# Nixie_Display.net
KiCad netlist of a schematic drawn in EAGLE
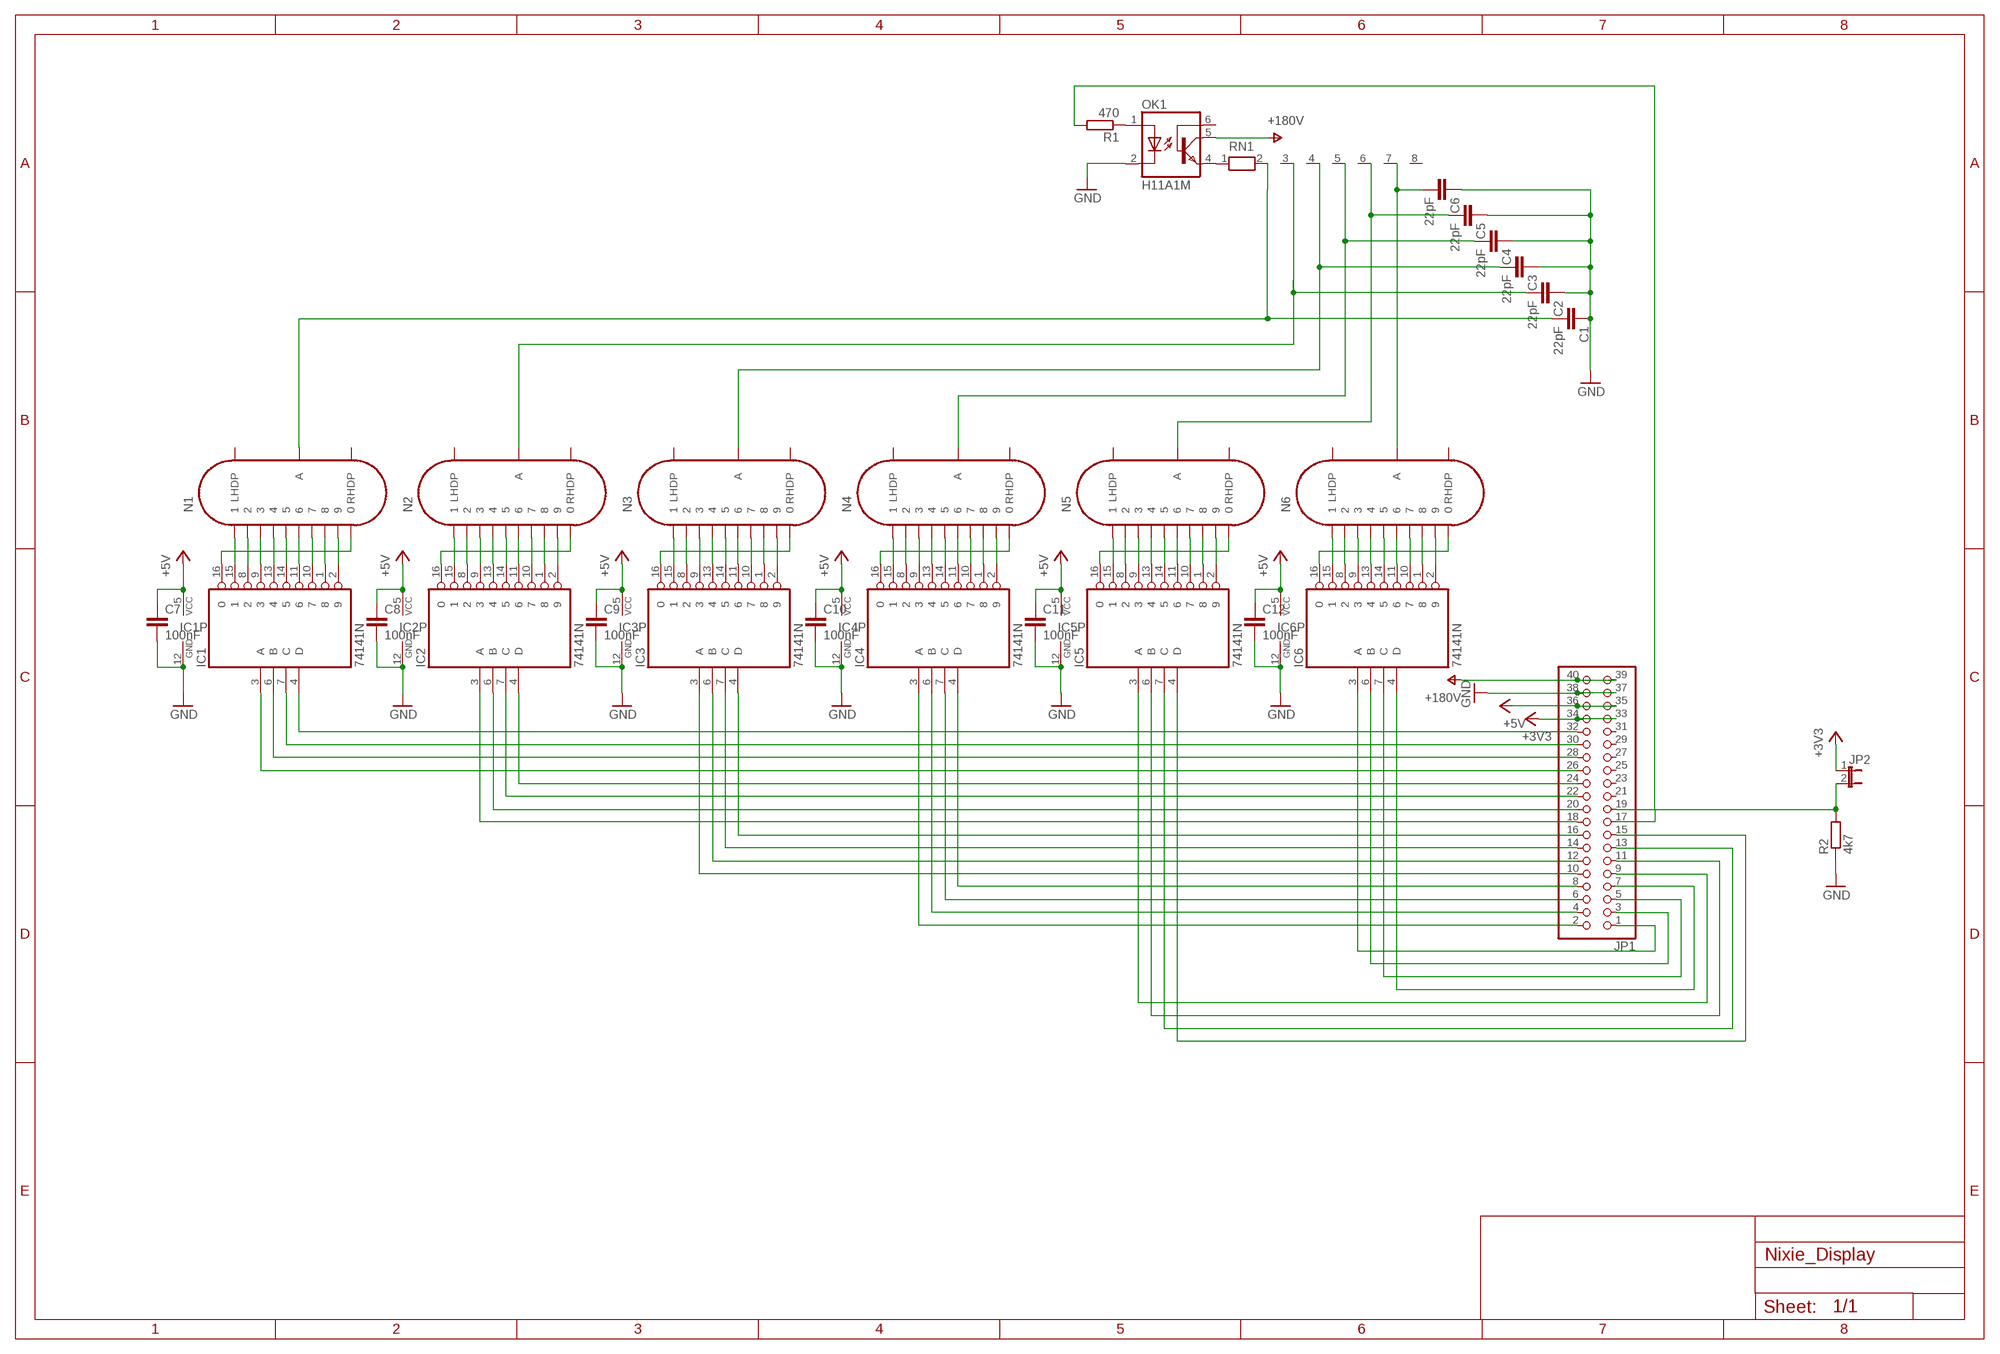
[diagram p0: schematic, sheet 1]

(export (version "E")
  (design (tool "Eeschema 10.0.6"))
  (components
    (comp (ref "C1")
      (value "22pF")
      (footprint "eagle-import:C025-025X050")
      (libsource (lib "eagle-import") (part "C-EU025-025X050"))
    )
    (comp (ref "C2")
      (value "22pF")
      (footprint "eagle-import:C025-025X050")
      (libsource (lib "eagle-import") (part "C-EU025-025X050"))
    )
    (comp (ref "C3")
      (value "22pF")
      (footprint "eagle-import:C025-025X050")
      (libsource (lib "eagle-import") (part "C-EU025-025X050"))
    )
    (comp (ref "C4")
      (value "22pF")
      (footprint "eagle-import:C025-025X050")
      (libsource (lib "eagle-import") (part "C-EU025-025X050"))
    )
    (comp (ref "C5")
      (value "22pF")
      (footprint "eagle-import:C025-025X050")
      (libsource (lib "eagle-import") (part "C-EU025-025X050"))
    )
    (comp (ref "C6")
      (value "22pF")
      (footprint "eagle-import:C025-025X050")
      (libsource (lib "eagle-import") (part "C-EU025-025X050"))
    )
    (comp (ref "C7")
      (value "100nF")
      (footprint "eagle-import:C050-025X075")
      (libsource (lib "eagle-import") (part "C-EU050-025X075"))
    )
    (comp (ref "C8")
      (value "100nF")
      (footprint "eagle-import:C050-025X075")
      (libsource (lib "eagle-import") (part "C-EU050-025X075"))
    )
    (comp (ref "C9")
      (value "100nF")
      (footprint "eagle-import:C050-025X075")
      (libsource (lib "eagle-import") (part "C-EU050-025X075"))
    )
    (comp (ref "C10")
      (value "100nF")
      (footprint "eagle-import:C050-025X075")
      (libsource (lib "eagle-import") (part "C-EU050-025X075"))
    )
    (comp (ref "C11")
      (value "100nF")
      (footprint "eagle-import:C050-025X075")
      (libsource (lib "eagle-import") (part "C-EU050-025X075"))
    )
    (comp (ref "C12")
      (value "100nF")
      (footprint "eagle-import:C050-025X075")
      (libsource (lib "eagle-import") (part "C-EU050-025X075"))
    )
    (comp (ref "IC1")
      (value "74141N")
      (footprint "eagle-import:DIL16")
      (libsource (lib "eagle-import") (part "74141N"))
    )
    (comp (ref "IC2")
      (value "74141N")
      (footprint "eagle-import:DIL16")
      (libsource (lib "eagle-import") (part "74141N"))
    )
    (comp (ref "IC3")
      (value "74141N")
      (footprint "eagle-import:DIL16")
      (libsource (lib "eagle-import") (part "74141N"))
    )
    (comp (ref "IC4")
      (value "74141N")
      (footprint "eagle-import:DIL16")
      (libsource (lib "eagle-import") (part "74141N"))
    )
    (comp (ref "IC5")
      (value "74141N")
      (footprint "eagle-import:DIL16")
      (libsource (lib "eagle-import") (part "74141N"))
    )
    (comp (ref "IC6")
      (value "74141N")
      (footprint "eagle-import:DIL16")
      (libsource (lib "eagle-import") (part "74141N"))
    )
    (comp (ref "JP1")
      (value "PINHD-2X20")
      (footprint "eagle-import:2X20")
      (libsource (lib "eagle-import") (part "PINHD-2X20"))
    )
    (comp (ref "JP2")
      (value "JP1E")
      (footprint "eagle-import:JP1")
      (libsource (lib "eagle-import") (part "JP1E"))
    )
    (comp (ref "N1")
      (value "IN-14")
      (footprint "eagle-import:IN-14")
      (libsource (lib "eagle-import") (part "IN-14"))
    )
    (comp (ref "N2")
      (value "IN-14")
      (footprint "eagle-import:IN-14")
      (libsource (lib "eagle-import") (part "IN-14"))
    )
    (comp (ref "N3")
      (value "IN-14")
      (footprint "eagle-import:IN-14")
      (libsource (lib "eagle-import") (part "IN-14"))
    )
    (comp (ref "N4")
      (value "IN-14")
      (footprint "eagle-import:IN-14")
      (libsource (lib "eagle-import") (part "IN-14"))
    )
    (comp (ref "N5")
      (value "IN-14")
      (footprint "eagle-import:IN-14")
      (libsource (lib "eagle-import") (part "IN-14"))
    )
    (comp (ref "N6")
      (value "IN-14")
      (footprint "eagle-import:IN-14")
      (libsource (lib "eagle-import") (part "IN-14"))
    )
    (comp (ref "OK1")
      (value "H11A1M")
      (footprint "eagle-import:DIL06")
      (fields (field (name "MPN") "H11A1-M"))
      (libsource (lib "eagle-import") (part "H11A?M1"))
    )
    (comp (ref "R1")
      (value "470")
      (footprint "eagle-import:0207_10")
      (libsource (lib "eagle-import") (part "R-EU_0207/10"))
    )
    (comp (ref "R2")
      (value "4k7")
      (footprint "eagle-import:0207_10")
      (libsource (lib "eagle-import") (part "R-EU_0207/10"))
    )
    (comp (ref "RN1")
      (value "RN07")
      (footprint "eagle-import:RN-8")
      (libsource (lib "eagle-import") (part "RN07"))
    )
  )
  (nets
    (net (code "1") (name "+3V3") (class "Default")
      (node (ref "JP1") (pin "33") (pinfunction "33_33") (pintype "passive"))
      (node (ref "JP1") (pin "34") (pinfunction "34_34") (pintype "passive"))
      (node (ref "JP2") (pin "1") (pinfunction "1_1") (pintype "passive"))
    )
    (net (code "2") (name "+5V") (class "Default")
      (node (ref "C10") (pin "1") (pinfunction "1_1") (pintype "passive"))
      (node (ref "C11") (pin "1") (pinfunction "1_1") (pintype "passive"))
      (node (ref "C12") (pin "1") (pinfunction "1_1") (pintype "passive"))
      (node (ref "C7") (pin "1") (pinfunction "1_1") (pintype "passive"))
      (node (ref "C8") (pin "1") (pinfunction "1_1") (pintype "passive"))
      (node (ref "C9") (pin "1") (pinfunction "1_1") (pintype "passive"))
      (node (ref "IC1") (pin "5") (pinfunction "VCC_5") (pintype "power_in"))
      (node (ref "IC2") (pin "5") (pinfunction "VCC_5") (pintype "power_in"))
      (node (ref "IC3") (pin "5") (pinfunction "VCC_5") (pintype "power_in"))
      (node (ref "IC4") (pin "5") (pinfunction "VCC_5") (pintype "power_in"))
      (node (ref "IC5") (pin "5") (pinfunction "VCC_5") (pintype "power_in"))
      (node (ref "IC6") (pin "5") (pinfunction "VCC_5") (pintype "power_in"))
      (node (ref "JP1") (pin "35") (pinfunction "35_35") (pintype "passive"))
      (node (ref "JP1") (pin "36") (pinfunction "36_36") (pintype "passive"))
    )
    (net (code "3") (name "+180V") (class "Default")
      (node (ref "JP1") (pin "39") (pinfunction "39_39") (pintype "passive"))
      (node (ref "JP1") (pin "40") (pinfunction "40_40") (pintype "passive"))
      (node (ref "OK1") (pin "5") (pinfunction "COL_5") (pintype "passive"))
    )
    (net (code "4") (name "GND") (class "Default")
      (node (ref "C1") (pin "1") (pinfunction "1_1") (pintype "passive"))
      (node (ref "C10") (pin "2") (pinfunction "2_2") (pintype "passive"))
      (node (ref "C11") (pin "2") (pinfunction "2_2") (pintype "passive"))
      (node (ref "C12") (pin "2") (pinfunction "2_2") (pintype "passive"))
      (node (ref "C2") (pin "1") (pinfunction "1_1") (pintype "passive"))
      (node (ref "C3") (pin "1") (pinfunction "1_1") (pintype "passive"))
      (node (ref "C4") (pin "1") (pinfunction "1_1") (pintype "passive"))
      (node (ref "C5") (pin "1") (pinfunction "1_1") (pintype "passive"))
      (node (ref "C6") (pin "1") (pinfunction "1_1") (pintype "passive"))
      (node (ref "C7") (pin "2") (pinfunction "2_2") (pintype "passive"))
      (node (ref "C8") (pin "2") (pinfunction "2_2") (pintype "passive"))
      (node (ref "C9") (pin "2") (pinfunction "2_2") (pintype "passive"))
      (node (ref "IC1") (pin "12") (pinfunction "GND_12") (pintype "power_in"))
      (node (ref "IC2") (pin "12") (pinfunction "GND_12") (pintype "power_in"))
      (node (ref "IC3") (pin "12") (pinfunction "GND_12") (pintype "power_in"))
      (node (ref "IC4") (pin "12") (pinfunction "GND_12") (pintype "power_in"))
      (node (ref "IC5") (pin "12") (pinfunction "GND_12") (pintype "power_in"))
      (node (ref "IC6") (pin "12") (pinfunction "GND_12") (pintype "power_in"))
      (node (ref "JP1") (pin "37") (pinfunction "37_37") (pintype "passive"))
      (node (ref "JP1") (pin "38") (pinfunction "38_38") (pintype "passive"))
      (node (ref "OK1") (pin "2") (pinfunction "C_2") (pintype "passive"))
      (node (ref "R2") (pin "1") (pinfunction "1_1") (pintype "passive"))
    )
    (net (code "5") (name "Net-(C1-Pad2)") (class "Default")
      (node (ref "C1") (pin "2") (pinfunction "2_2") (pintype "passive"))
      (node (ref "N1") (pin "A") (pinfunction "A_A") (pintype "bidirectional"))
      (node (ref "RN1") (pin "2") (pinfunction "2_2") (pintype "passive"))
    )
    (net (code "6") (name "Net-(C2-Pad2)") (class "Default")
      (node (ref "C2") (pin "2") (pinfunction "2_2") (pintype "passive"))
      (node (ref "N2") (pin "A") (pinfunction "A_A") (pintype "bidirectional"))
      (node (ref "RN1") (pin "3") (pinfunction "3_3") (pintype "passive"))
    )
    (net (code "7") (name "Net-(C3-Pad2)") (class "Default")
      (node (ref "C3") (pin "2") (pinfunction "2_2") (pintype "passive"))
      (node (ref "N3") (pin "A") (pinfunction "A_A") (pintype "bidirectional"))
      (node (ref "RN1") (pin "4") (pinfunction "4_4") (pintype "passive"))
    )
    (net (code "8") (name "Net-(C4-Pad2)") (class "Default")
      (node (ref "C4") (pin "2") (pinfunction "2_2") (pintype "passive"))
      (node (ref "N4") (pin "A") (pinfunction "A_A") (pintype "bidirectional"))
      (node (ref "RN1") (pin "5") (pinfunction "5_5") (pintype "passive"))
    )
    (net (code "9") (name "Net-(C5-Pad2)") (class "Default")
      (node (ref "C5") (pin "2") (pinfunction "2_2") (pintype "passive"))
      (node (ref "N5") (pin "A") (pinfunction "A_A") (pintype "bidirectional"))
      (node (ref "RN1") (pin "6") (pinfunction "6_6") (pintype "passive"))
    )
    (net (code "10") (name "Net-(C6-Pad2)") (class "Default")
      (node (ref "C6") (pin "2") (pinfunction "2_2") (pintype "passive"))
      (node (ref "N6") (pin "A") (pinfunction "A_A") (pintype "bidirectional"))
      (node (ref "RN1") (pin "7") (pinfunction "7_7") (pintype "passive"))
    )
    (net (code "11") (name "Net-(IC1A-0)") (class "Default")
      (node (ref "IC1") (pin "16") (pinfunction "0_16") (pintype "open_collector"))
      (node (ref "N1") (pin "0") (pinfunction "0_0") (pintype "bidirectional"))
    )
    (net (code "12") (name "Net-(IC1A-1)") (class "Default")
      (node (ref "IC1") (pin "15") (pinfunction "1_15") (pintype "open_collector"))
      (node (ref "N1") (pin "1") (pinfunction "1_1") (pintype "bidirectional"))
    )
    (net (code "13") (name "Net-(IC1A-2)") (class "Default")
      (node (ref "IC1") (pin "8") (pinfunction "2_8") (pintype "open_collector"))
      (node (ref "N1") (pin "2") (pinfunction "2_2") (pintype "bidirectional"))
    )
    (net (code "14") (name "Net-(IC1A-3)") (class "Default")
      (node (ref "IC1") (pin "9") (pinfunction "3_9") (pintype "open_collector"))
      (node (ref "N1") (pin "3") (pinfunction "3_3") (pintype "bidirectional"))
    )
    (net (code "15") (name "Net-(IC1A-4)") (class "Default")
      (node (ref "IC1") (pin "13") (pinfunction "4_13") (pintype "open_collector"))
      (node (ref "N1") (pin "4") (pinfunction "4_4") (pintype "bidirectional"))
    )
    (net (code "16") (name "Net-(IC1A-5)") (class "Default")
      (node (ref "IC1") (pin "14") (pinfunction "5_14") (pintype "open_collector"))
      (node (ref "N1") (pin "5") (pinfunction "5_5") (pintype "bidirectional"))
    )
    (net (code "17") (name "Net-(IC1A-6)") (class "Default")
      (node (ref "IC1") (pin "11") (pinfunction "6_11") (pintype "open_collector"))
      (node (ref "N1") (pin "6") (pinfunction "6_6") (pintype "bidirectional"))
    )
    (net (code "18") (name "Net-(IC1A-7)") (class "Default")
      (node (ref "IC1") (pin "10") (pinfunction "7_10") (pintype "open_collector"))
      (node (ref "N1") (pin "7") (pinfunction "7_7") (pintype "bidirectional"))
    )
    (net (code "19") (name "Net-(IC1A-8)") (class "Default")
      (node (ref "IC1") (pin "1") (pinfunction "8_1") (pintype "open_collector"))
      (node (ref "N1") (pin "8") (pinfunction "8_8") (pintype "bidirectional"))
    )
    (net (code "20") (name "Net-(IC1A-9)") (class "Default")
      (node (ref "IC1") (pin "2") (pinfunction "9_2") (pintype "open_collector"))
      (node (ref "N1") (pin "9") (pinfunction "9_9") (pintype "bidirectional"))
    )
    (net (code "21") (name "Net-(IC1A-A)") (class "Default")
      (node (ref "IC1") (pin "3") (pinfunction "A_3") (pintype "input"))
      (node (ref "JP1") (pin "26") (pinfunction "26_26") (pintype "passive"))
    )
    (net (code "22") (name "Net-(IC1A-B)") (class "Default")
      (node (ref "IC1") (pin "6") (pinfunction "B_6") (pintype "input"))
      (node (ref "JP1") (pin "28") (pinfunction "28_28") (pintype "passive"))
    )
    (net (code "23") (name "Net-(IC1A-C)") (class "Default")
      (node (ref "IC1") (pin "7") (pinfunction "C_7") (pintype "input"))
      (node (ref "JP1") (pin "30") (pinfunction "30_30") (pintype "passive"))
    )
    (net (code "24") (name "Net-(IC1A-D)") (class "Default")
      (node (ref "IC1") (pin "4") (pinfunction "D_4") (pintype "input"))
      (node (ref "JP1") (pin "32") (pinfunction "32_32") (pintype "passive"))
    )
    (net (code "25") (name "Net-(IC2A-0)") (class "Default")
      (node (ref "IC2") (pin "16") (pinfunction "0_16") (pintype "open_collector"))
      (node (ref "N2") (pin "0") (pinfunction "0_0") (pintype "bidirectional"))
    )
    (net (code "26") (name "Net-(IC2A-1)") (class "Default")
      (node (ref "IC2") (pin "15") (pinfunction "1_15") (pintype "open_collector"))
      (node (ref "N2") (pin "1") (pinfunction "1_1") (pintype "bidirectional"))
    )
    (net (code "27") (name "Net-(IC2A-2)") (class "Default")
      (node (ref "IC2") (pin "8") (pinfunction "2_8") (pintype "open_collector"))
      (node (ref "N2") (pin "2") (pinfunction "2_2") (pintype "bidirectional"))
    )
    (net (code "28") (name "Net-(IC2A-3)") (class "Default")
      (node (ref "IC2") (pin "9") (pinfunction "3_9") (pintype "open_collector"))
      (node (ref "N2") (pin "3") (pinfunction "3_3") (pintype "bidirectional"))
    )
    (net (code "29") (name "Net-(IC2A-4)") (class "Default")
      (node (ref "IC2") (pin "13") (pinfunction "4_13") (pintype "open_collector"))
      (node (ref "N2") (pin "4") (pinfunction "4_4") (pintype "bidirectional"))
    )
    (net (code "30") (name "Net-(IC2A-5)") (class "Default")
      (node (ref "IC2") (pin "14") (pinfunction "5_14") (pintype "open_collector"))
      (node (ref "N2") (pin "5") (pinfunction "5_5") (pintype "bidirectional"))
    )
    (net (code "31") (name "Net-(IC2A-6)") (class "Default")
      (node (ref "IC2") (pin "11") (pinfunction "6_11") (pintype "open_collector"))
      (node (ref "N2") (pin "6") (pinfunction "6_6") (pintype "bidirectional"))
    )
    (net (code "32") (name "Net-(IC2A-7)") (class "Default")
      (node (ref "IC2") (pin "10") (pinfunction "7_10") (pintype "open_collector"))
      (node (ref "N2") (pin "7") (pinfunction "7_7") (pintype "bidirectional"))
    )
    (net (code "33") (name "Net-(IC2A-8)") (class "Default")
      (node (ref "IC2") (pin "1") (pinfunction "8_1") (pintype "open_collector"))
      (node (ref "N2") (pin "8") (pinfunction "8_8") (pintype "bidirectional"))
    )
    (net (code "34") (name "Net-(IC2A-9)") (class "Default")
      (node (ref "IC2") (pin "2") (pinfunction "9_2") (pintype "open_collector"))
      (node (ref "N2") (pin "9") (pinfunction "9_9") (pintype "bidirectional"))
    )
    (net (code "35") (name "Net-(IC2A-A)") (class "Default")
      (node (ref "IC2") (pin "3") (pinfunction "A_3") (pintype "input"))
      (node (ref "JP1") (pin "18") (pinfunction "18_18") (pintype "passive"))
    )
    (net (code "36") (name "Net-(IC2A-B)") (class "Default")
      (node (ref "IC2") (pin "6") (pinfunction "B_6") (pintype "input"))
      (node (ref "JP1") (pin "20") (pinfunction "20_20") (pintype "passive"))
    )
    (net (code "37") (name "Net-(IC2A-C)") (class "Default")
      (node (ref "IC2") (pin "7") (pinfunction "C_7") (pintype "input"))
      (node (ref "JP1") (pin "22") (pinfunction "22_22") (pintype "passive"))
    )
    (net (code "38") (name "Net-(IC2A-D)") (class "Default")
      (node (ref "IC2") (pin "4") (pinfunction "D_4") (pintype "input"))
      (node (ref "JP1") (pin "24") (pinfunction "24_24") (pintype "passive"))
    )
    (net (code "39") (name "Net-(IC3A-0)") (class "Default")
      (node (ref "IC3") (pin "16") (pinfunction "0_16") (pintype "open_collector"))
      (node (ref "N3") (pin "0") (pinfunction "0_0") (pintype "bidirectional"))
    )
    (net (code "40") (name "Net-(IC3A-1)") (class "Default")
      (node (ref "IC3") (pin "15") (pinfunction "1_15") (pintype "open_collector"))
      (node (ref "N3") (pin "1") (pinfunction "1_1") (pintype "bidirectional"))
    )
    (net (code "41") (name "Net-(IC3A-2)") (class "Default")
      (node (ref "IC3") (pin "8") (pinfunction "2_8") (pintype "open_collector"))
      (node (ref "N3") (pin "2") (pinfunction "2_2") (pintype "bidirectional"))
    )
    (net (code "42") (name "Net-(IC3A-3)") (class "Default")
      (node (ref "IC3") (pin "9") (pinfunction "3_9") (pintype "open_collector"))
      (node (ref "N3") (pin "3") (pinfunction "3_3") (pintype "bidirectional"))
    )
    (net (code "43") (name "Net-(IC3A-4)") (class "Default")
      (node (ref "IC3") (pin "13") (pinfunction "4_13") (pintype "open_collector"))
      (node (ref "N3") (pin "4") (pinfunction "4_4") (pintype "bidirectional"))
    )
    (net (code "44") (name "Net-(IC3A-5)") (class "Default")
      (node (ref "IC3") (pin "14") (pinfunction "5_14") (pintype "open_collector"))
      (node (ref "N3") (pin "5") (pinfunction "5_5") (pintype "bidirectional"))
    )
    (net (code "45") (name "Net-(IC3A-6)") (class "Default")
      (node (ref "IC3") (pin "11") (pinfunction "6_11") (pintype "open_collector"))
      (node (ref "N3") (pin "6") (pinfunction "6_6") (pintype "bidirectional"))
    )
    (net (code "46") (name "Net-(IC3A-7)") (class "Default")
      (node (ref "IC3") (pin "10") (pinfunction "7_10") (pintype "open_collector"))
      (node (ref "N3") (pin "7") (pinfunction "7_7") (pintype "bidirectional"))
    )
    (net (code "47") (name "Net-(IC3A-8)") (class "Default")
      (node (ref "IC3") (pin "1") (pinfunction "8_1") (pintype "open_collector"))
      (node (ref "N3") (pin "8") (pinfunction "8_8") (pintype "bidirectional"))
    )
    (net (code "48") (name "Net-(IC3A-9)") (class "Default")
      (node (ref "IC3") (pin "2") (pinfunction "9_2") (pintype "open_collector"))
      (node (ref "N3") (pin "9") (pinfunction "9_9") (pintype "bidirectional"))
    )
    (net (code "49") (name "Net-(IC3A-A)") (class "Default")
      (node (ref "IC3") (pin "3") (pinfunction "A_3") (pintype "input"))
      (node (ref "JP1") (pin "10") (pinfunction "10_10") (pintype "passive"))
    )
    (net (code "50") (name "Net-(IC3A-B)") (class "Default")
      (node (ref "IC3") (pin "6") (pinfunction "B_6") (pintype "input"))
      (node (ref "JP1") (pin "12") (pinfunction "12_12") (pintype "passive"))
    )
    (net (code "51") (name "Net-(IC3A-C)") (class "Default")
      (node (ref "IC3") (pin "7") (pinfunction "C_7") (pintype "input"))
      (node (ref "JP1") (pin "14") (pinfunction "14_14") (pintype "passive"))
    )
    (net (code "52") (name "Net-(IC3A-D)") (class "Default")
      (node (ref "IC3") (pin "4") (pinfunction "D_4") (pintype "input"))
      (node (ref "JP1") (pin "16") (pinfunction "16_16") (pintype "passive"))
    )
    (net (code "53") (name "Net-(IC4A-0)") (class "Default")
      (node (ref "IC4") (pin "16") (pinfunction "0_16") (pintype "open_collector"))
      (node (ref "N4") (pin "0") (pinfunction "0_0") (pintype "bidirectional"))
    )
    (net (code "54") (name "Net-(IC4A-1)") (class "Default")
      (node (ref "IC4") (pin "15") (pinfunction "1_15") (pintype "open_collector"))
      (node (ref "N4") (pin "1") (pinfunction "1_1") (pintype "bidirectional"))
    )
    (net (code "55") (name "Net-(IC4A-2)") (class "Default")
      (node (ref "IC4") (pin "8") (pinfunction "2_8") (pintype "open_collector"))
      (node (ref "N4") (pin "2") (pinfunction "2_2") (pintype "bidirectional"))
    )
    (net (code "56") (name "Net-(IC4A-3)") (class "Default")
      (node (ref "IC4") (pin "9") (pinfunction "3_9") (pintype "open_collector"))
      (node (ref "N4") (pin "3") (pinfunction "3_3") (pintype "bidirectional"))
    )
    (net (code "57") (name "Net-(IC4A-4)") (class "Default")
      (node (ref "IC4") (pin "13") (pinfunction "4_13") (pintype "open_collector"))
      (node (ref "N4") (pin "4") (pinfunction "4_4") (pintype "bidirectional"))
    )
    (net (code "58") (name "Net-(IC4A-5)") (class "Default")
      (node (ref "IC4") (pin "14") (pinfunction "5_14") (pintype "open_collector"))
      (node (ref "N4") (pin "5") (pinfunction "5_5") (pintype "bidirectional"))
    )
    (net (code "59") (name "Net-(IC4A-6)") (class "Default")
      (node (ref "IC4") (pin "11") (pinfunction "6_11") (pintype "open_collector"))
      (node (ref "N4") (pin "6") (pinfunction "6_6") (pintype "bidirectional"))
    )
    (net (code "60") (name "Net-(IC4A-7)") (class "Default")
      (node (ref "IC4") (pin "10") (pinfunction "7_10") (pintype "open_collector"))
      (node (ref "N4") (pin "7") (pinfunction "7_7") (pintype "bidirectional"))
    )
    (net (code "61") (name "Net-(IC4A-8)") (class "Default")
      (node (ref "IC4") (pin "1") (pinfunction "8_1") (pintype "open_collector"))
      (node (ref "N4") (pin "8") (pinfunction "8_8") (pintype "bidirectional"))
    )
    (net (code "62") (name "Net-(IC4A-9)") (class "Default")
      (node (ref "IC4") (pin "2") (pinfunction "9_2") (pintype "open_collector"))
      (node (ref "N4") (pin "9") (pinfunction "9_9") (pintype "bidirectional"))
    )
    (net (code "63") (name "Net-(IC4A-A)") (class "Default")
      (node (ref "IC4") (pin "3") (pinfunction "A_3") (pintype "input"))
      (node (ref "JP1") (pin "2") (pinfunction "2_2") (pintype "passive"))
    )
    (net (code "64") (name "Net-(IC4A-B)") (class "Default")
      (node (ref "IC4") (pin "6") (pinfunction "B_6") (pintype "input"))
      (node (ref "JP1") (pin "4") (pinfunction "4_4") (pintype "passive"))
    )
    (net (code "65") (name "Net-(IC4A-C)") (class "Default")
      (node (ref "IC4") (pin "7") (pinfunction "C_7") (pintype "input"))
      (node (ref "JP1") (pin "6") (pinfunction "6_6") (pintype "passive"))
    )
    (net (code "66") (name "Net-(IC4A-D)") (class "Default")
      (node (ref "IC4") (pin "4") (pinfunction "D_4") (pintype "input"))
      (node (ref "JP1") (pin "8") (pinfunction "8_8") (pintype "passive"))
    )
    (net (code "67") (name "Net-(IC5A-0)") (class "Default")
      (node (ref "IC5") (pin "16") (pinfunction "0_16") (pintype "open_collector"))
      (node (ref "N5") (pin "0") (pinfunction "0_0") (pintype "bidirectional"))
    )
    (net (code "68") (name "Net-(IC5A-1)") (class "Default")
      (node (ref "IC5") (pin "15") (pinfunction "1_15") (pintype "open_collector"))
      (node (ref "N5") (pin "1") (pinfunction "1_1") (pintype "bidirectional"))
    )
    (net (code "69") (name "Net-(IC5A-2)") (class "Default")
      (node (ref "IC5") (pin "8") (pinfunction "2_8") (pintype "open_collector"))
      (node (ref "N5") (pin "2") (pinfunction "2_2") (pintype "bidirectional"))
    )
    (net (code "70") (name "Net-(IC5A-3)") (class "Default")
      (node (ref "IC5") (pin "9") (pinfunction "3_9") (pintype "open_collector"))
      (node (ref "N5") (pin "3") (pinfunction "3_3") (pintype "bidirectional"))
    )
    (net (code "71") (name "Net-(IC5A-4)") (class "Default")
      (node (ref "IC5") (pin "13") (pinfunction "4_13") (pintype "open_collector"))
      (node (ref "N5") (pin "4") (pinfunction "4_4") (pintype "bidirectional"))
    )
    (net (code "72") (name "Net-(IC5A-5)") (class "Default")
      (node (ref "IC5") (pin "14") (pinfunction "5_14") (pintype "open_collector"))
      (node (ref "N5") (pin "5") (pinfunction "5_5") (pintype "bidirectional"))
    )
    (net (code "73") (name "Net-(IC5A-6)") (class "Default")
      (node (ref "IC5") (pin "11") (pinfunction "6_11") (pintype "open_collector"))
      (node (ref "N5") (pin "6") (pinfunction "6_6") (pintype "bidirectional"))
    )
    (net (code "74") (name "Net-(IC5A-7)") (class "Default")
      (node (ref "IC5") (pin "10") (pinfunction "7_10") (pintype "open_collector"))
      (node (ref "N5") (pin "7") (pinfunction "7_7") (pintype "bidirectional"))
    )
    (net (code "75") (name "Net-(IC5A-8)") (class "Default")
      (node (ref "IC5") (pin "1") (pinfunction "8_1") (pintype "open_collector"))
      (node (ref "N5") (pin "8") (pinfunction "8_8") (pintype "bidirectional"))
    )
    (net (code "76") (name "Net-(IC5A-9)") (class "Default")
      (node (ref "IC5") (pin "2") (pinfunction "9_2") (pintype "open_collector"))
      (node (ref "N5") (pin "9") (pinfunction "9_9") (pintype "bidirectional"))
    )
    (net (code "77") (name "Net-(IC5A-A)") (class "Default")
      (node (ref "IC5") (pin "3") (pinfunction "A_3") (pintype "input"))
      (node (ref "JP1") (pin "9") (pinfunction "9_9") (pintype "passive"))
    )
    (net (code "78") (name "Net-(IC5A-B)") (class "Default")
      (node (ref "IC5") (pin "6") (pinfunction "B_6") (pintype "input"))
      (node (ref "JP1") (pin "11") (pinfunction "11_11") (pintype "passive"))
    )
    (net (code "79") (name "Net-(IC5A-C)") (class "Default")
      (node (ref "IC5") (pin "7") (pinfunction "C_7") (pintype "input"))
      (node (ref "JP1") (pin "13") (pinfunction "13_13") (pintype "passive"))
    )
    (net (code "80") (name "Net-(IC5A-D)") (class "Default")
      (node (ref "IC5") (pin "4") (pinfunction "D_4") (pintype "input"))
      (node (ref "JP1") (pin "15") (pinfunction "15_15") (pintype "passive"))
    )
    (net (code "81") (name "Net-(IC6A-0)") (class "Default")
      (node (ref "IC6") (pin "16") (pinfunction "0_16") (pintype "open_collector"))
      (node (ref "N6") (pin "0") (pinfunction "0_0") (pintype "bidirectional"))
    )
    (net (code "82") (name "Net-(IC6A-1)") (class "Default")
      (node (ref "IC6") (pin "15") (pinfunction "1_15") (pintype "open_collector"))
      (node (ref "N6") (pin "1") (pinfunction "1_1") (pintype "bidirectional"))
    )
    (net (code "83") (name "Net-(IC6A-2)") (class "Default")
      (node (ref "IC6") (pin "8") (pinfunction "2_8") (pintype "open_collector"))
      (node (ref "N6") (pin "2") (pinfunction "2_2") (pintype "bidirectional"))
    )
    (net (code "84") (name "Net-(IC6A-3)") (class "Default")
      (node (ref "IC6") (pin "9") (pinfunction "3_9") (pintype "open_collector"))
      (node (ref "N6") (pin "3") (pinfunction "3_3") (pintype "bidirectional"))
    )
    (net (code "85") (name "Net-(IC6A-4)") (class "Default")
      (node (ref "IC6") (pin "13") (pinfunction "4_13") (pintype "open_collector"))
      (node (ref "N6") (pin "4") (pinfunction "4_4") (pintype "bidirectional"))
    )
    (net (code "86") (name "Net-(IC6A-5)") (class "Default")
      (node (ref "IC6") (pin "14") (pinfunction "5_14") (pintype "open_collector"))
      (node (ref "N6") (pin "5") (pinfunction "5_5") (pintype "bidirectional"))
    )
    (net (code "87") (name "Net-(IC6A-6)") (class "Default")
      (node (ref "IC6") (pin "11") (pinfunction "6_11") (pintype "open_collector"))
      (node (ref "N6") (pin "6") (pinfunction "6_6") (pintype "bidirectional"))
    )
    (net (code "88") (name "Net-(IC6A-7)") (class "Default")
      (node (ref "IC6") (pin "10") (pinfunction "7_10") (pintype "open_collector"))
      (node (ref "N6") (pin "7") (pinfunction "7_7") (pintype "bidirectional"))
    )
    (net (code "89") (name "Net-(IC6A-8)") (class "Default")
      (node (ref "IC6") (pin "1") (pinfunction "8_1") (pintype "open_collector"))
      (node (ref "N6") (pin "8") (pinfunction "8_8") (pintype "bidirectional"))
    )
    (net (code "90") (name "Net-(IC6A-9)") (class "Default")
      (node (ref "IC6") (pin "2") (pinfunction "9_2") (pintype "open_collector"))
      (node (ref "N6") (pin "9") (pinfunction "9_9") (pintype "bidirectional"))
    )
    (net (code "91") (name "Net-(IC6A-A)") (class "Default")
      (node (ref "IC6") (pin "3") (pinfunction "A_3") (pintype "input"))
      (node (ref "JP1") (pin "1") (pinfunction "1_1") (pintype "passive"))
    )
    (net (code "92") (name "Net-(IC6A-B)") (class "Default")
      (node (ref "IC6") (pin "6") (pinfunction "B_6") (pintype "input"))
      (node (ref "JP1") (pin "3") (pinfunction "3_3") (pintype "passive"))
    )
    (net (code "93") (name "Net-(IC6A-C)") (class "Default")
      (node (ref "IC6") (pin "7") (pinfunction "C_7") (pintype "input"))
      (node (ref "JP1") (pin "5") (pinfunction "5_5") (pintype "passive"))
    )
    (net (code "94") (name "Net-(IC6A-D)") (class "Default")
      (node (ref "IC6") (pin "4") (pinfunction "D_4") (pintype "input"))
      (node (ref "JP1") (pin "7") (pinfunction "7_7") (pintype "passive"))
    )
    (net (code "95") (name "Net-(JP1-Pad17)") (class "Default")
      (node (ref "JP1") (pin "17") (pinfunction "17_17") (pintype "passive"))
      (node (ref "R1") (pin "2") (pinfunction "2_2") (pintype "passive"))
    )
    (net (code "96") (name "Net-(JP1-Pad19)") (class "Default")
      (node (ref "JP1") (pin "19") (pinfunction "19_19") (pintype "passive"))
      (node (ref "JP2") (pin "2") (pinfunction "2_2") (pintype "passive"))
      (node (ref "R2") (pin "2") (pinfunction "2_2") (pintype "passive"))
    )
    (net (code "97") (name "Net-(OK1-A)") (class "Default")
      (node (ref "OK1") (pin "1") (pinfunction "A_1") (pintype "passive"))
      (node (ref "R1") (pin "1") (pinfunction "1_1") (pintype "passive"))
    )
    (net (code "98") (name "Net-(OK1-EMI)") (class "Default")
      (node (ref "OK1") (pin "4") (pinfunction "EMI_4") (pintype "passive"))
      (node (ref "RN1") (pin "1") (pinfunction "1_1") (pintype "passive"))
    )
    (net (code "99") (name "unconnected-(JP1-Pad21)") (class "Default")
      (node (ref "JP1") (pin "21") (pinfunction "21_21") (pintype "passive"))
    )
    (net (code "100") (name "unconnected-(JP1-Pad23)") (class "Default")
      (node (ref "JP1") (pin "23") (pinfunction "23_23") (pintype "passive"))
    )
    (net (code "101") (name "unconnected-(JP1-Pad25)") (class "Default")
      (node (ref "JP1") (pin "25") (pinfunction "25_25") (pintype "passive"))
    )
    (net (code "102") (name "unconnected-(JP1-Pad27)") (class "Default")
      (node (ref "JP1") (pin "27") (pinfunction "27_27") (pintype "passive"))
    )
    (net (code "103") (name "unconnected-(JP1-Pad29)") (class "Default")
      (node (ref "JP1") (pin "29") (pinfunction "29_29") (pintype "passive"))
    )
    (net (code "104") (name "unconnected-(JP1-Pad31)") (class "Default")
      (node (ref "JP1") (pin "31") (pinfunction "31_31") (pintype "passive"))
    )
    (net (code "105") (name "unconnected-(N1-PadLHDP)") (class "Default")
      (node (ref "N1") (pin "LHDP") (pinfunction "LHDP_LHDP") (pintype "bidirectional"))
    )
    (net (code "106") (name "unconnected-(N1-PadRHDP)") (class "Default")
      (node (ref "N1") (pin "RHDP") (pinfunction "RHDP_RHDP") (pintype "bidirectional"))
    )
    (net (code "107") (name "unconnected-(N2-PadLHDP)") (class "Default")
      (node (ref "N2") (pin "LHDP") (pinfunction "LHDP_LHDP") (pintype "bidirectional"))
    )
    (net (code "108") (name "unconnected-(N2-PadRHDP)") (class "Default")
      (node (ref "N2") (pin "RHDP") (pinfunction "RHDP_RHDP") (pintype "bidirectional"))
    )
    (net (code "109") (name "unconnected-(N3-PadLHDP)") (class "Default")
      (node (ref "N3") (pin "LHDP") (pinfunction "LHDP_LHDP") (pintype "bidirectional"))
    )
    (net (code "110") (name "unconnected-(N3-PadRHDP)") (class "Default")
      (node (ref "N3") (pin "RHDP") (pinfunction "RHDP_RHDP") (pintype "bidirectional"))
    )
    (net (code "111") (name "unconnected-(N4-PadLHDP)") (class "Default")
      (node (ref "N4") (pin "LHDP") (pinfunction "LHDP_LHDP") (pintype "bidirectional"))
    )
    (net (code "112") (name "unconnected-(N4-PadRHDP)") (class "Default")
      (node (ref "N4") (pin "RHDP") (pinfunction "RHDP_RHDP") (pintype "bidirectional"))
    )
    (net (code "113") (name "unconnected-(N5-PadLHDP)") (class "Default")
      (node (ref "N5") (pin "LHDP") (pinfunction "LHDP_LHDP") (pintype "bidirectional"))
    )
    (net (code "114") (name "unconnected-(N5-PadRHDP)") (class "Default")
      (node (ref "N5") (pin "RHDP") (pinfunction "RHDP_RHDP") (pintype "bidirectional"))
    )
    (net (code "115") (name "unconnected-(N6-PadLHDP)") (class "Default")
      (node (ref "N6") (pin "LHDP") (pinfunction "LHDP_LHDP") (pintype "bidirectional"))
    )
    (net (code "116") (name "unconnected-(N6-PadRHDP)") (class "Default")
      (node (ref "N6") (pin "RHDP") (pinfunction "RHDP_RHDP") (pintype "bidirectional"))
    )
    (net (code "117") (name "unconnected-(OK1-BAS-Pad6)") (class "Default")
      (node (ref "OK1") (pin "6") (pinfunction "BAS_6") (pintype "passive"))
    )
    (net (code "118") (name "unconnected-(RN1-Pad8)") (class "Default")
      (node (ref "RN1") (pin "8") (pinfunction "8_8") (pintype "passive"))
    )
  )
)
